# Display.net
KiCad netlist of a schematic drawn in Altium Designer
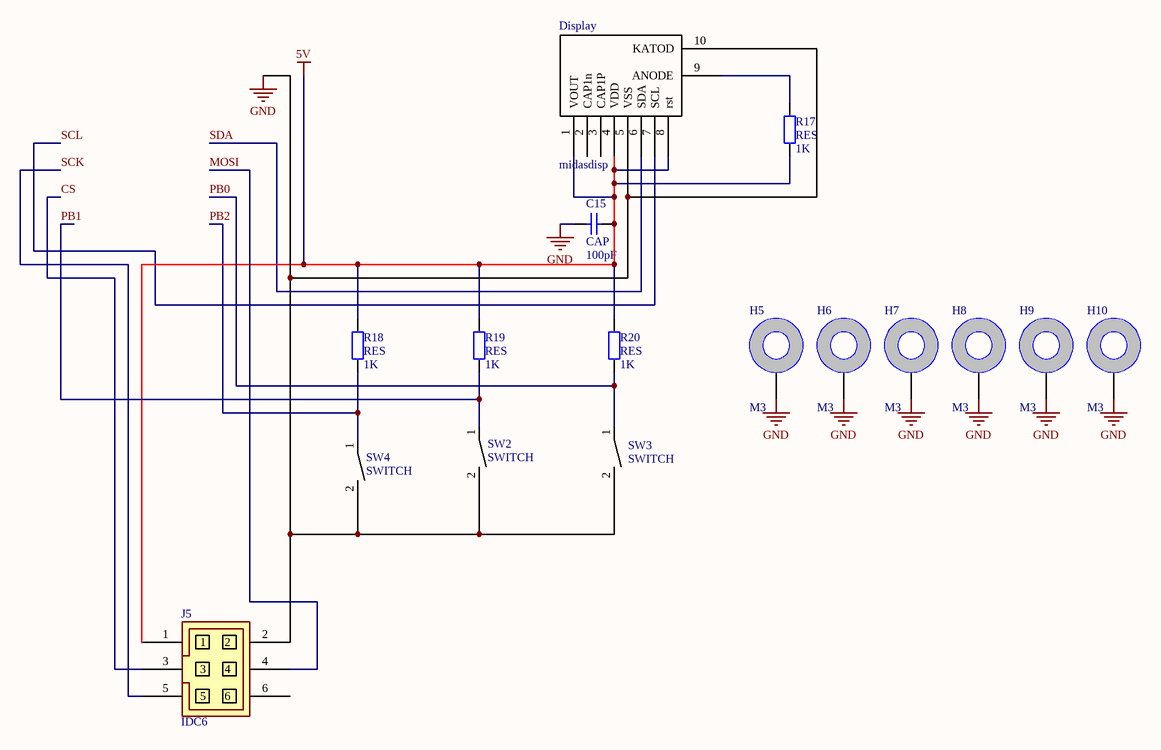
[diagram p0: Display.SchDoc]

(export (version "E")
  (design (tool "Eeschema 10.0.6"))
  (components
    (comp (ref "C15")
      (value "CAP")
      (footprint "CAPC1608X08M")
      (description "Capacitor")
      (fields (field (name "ALTIUM_VALUE") "100pF") (field (name "PUBLISHER") "Altium Limited"))
      (libsource (lib "std") (part "CAP"))
    )
    (comp (ref "Display")
      (value "midasdisp")
      (footprint "Display")
      (libsource (lib "MIDOSDISP") (part "midasdisp"))
    )
    (comp (ref "H5") (value "M3") (footprint "MOUNT_M3") (libsource (lib "std") (part "MOUNT_M3")))
    (comp (ref "H6") (value "M3") (footprint "MOUNT_M3") (libsource (lib "std") (part "MOUNT_M3")))
    (comp (ref "H7") (value "M3") (footprint "MOUNT_M3") (libsource (lib "std") (part "MOUNT_M3")))
    (comp (ref "H8") (value "M3") (footprint "MOUNT_M3") (libsource (lib "std") (part "MOUNT_M3")))
    (comp (ref "H9") (value "M3") (footprint "MOUNT_M3") (libsource (lib "std") (part "MOUNT_M3")))
    (comp (ref "H10") (value "M3") (footprint "MOUNT_M3") (libsource (lib "std") (part "MOUNT_M3")))
    (comp (ref "J5")
      (value "IDC6")
      (footprint "IDC6")
      (description "6pin IDC connector")
      (libsource (lib "std") (part "IDC6"))
    )
    (comp (ref "R17")
      (value "RES")
      (footprint "RESC1608X06M")
      (description "Resistor")
      (fields (field (name "ALTIUM_VALUE") "1K") (field (name "PUBLISHER") "Altium Limited"))
      (libsource (lib "std") (part "RES"))
    )
    (comp (ref "R18")
      (value "RES")
      (footprint "RESC1608X06M")
      (description "Resistor")
      (fields (field (name "ALTIUM_VALUE") "1K") (field (name "PUBLISHER") "Altium Limited"))
      (libsource (lib "std") (part "RES"))
    )
    (comp (ref "R19")
      (value "RES")
      (footprint "RESC1608X06M")
      (description "Resistor")
      (fields (field (name "ALTIUM_VALUE") "1K") (field (name "PUBLISHER") "Altium Limited"))
      (libsource (lib "std") (part "RES"))
    )
    (comp (ref "R20")
      (value "RES")
      (footprint "RESC1608X06M")
      (description "Resistor")
      (fields (field (name "ALTIUM_VALUE") "1K") (field (name "PUBLISHER") "Altium Limited"))
      (libsource (lib "std") (part "RES"))
    )
    (comp (ref "SW2")
      (value "SWITCH")
      (footprint "Switch_pad")
      (description "Switch")
      (libsource (lib "std") (part "Switch"))
    )
    (comp (ref "SW3")
      (value "SWITCH")
      (footprint "Switch_pad")
      (description "Switch")
      (libsource (lib "std") (part "Switch"))
    )
    (comp (ref "SW4")
      (value "SWITCH")
      (footprint "Switch_pad")
      (description "Switch")
      (libsource (lib "std") (part "Switch"))
    )
  )
  (nets
    (net (code "1") (name "/CS") (class "Default")
      (node (ref "J5") (pin "3") (pinfunction "3_3") (pintype "passive"))
    )
    (net (code "2") (name "/MOSI") (class "Default")
      (node (ref "J5") (pin "4") (pinfunction "4_4") (pintype "passive"))
    )
    (net (code "3") (name "/PB0") (class "Default")
      (node (ref "R20") (pin "1") (pinfunction "1_1") (pintype "passive"))
      (node (ref "SW3") (pin "1") (pinfunction "1_1") (pintype "passive"))
    )
    (net (code "4") (name "/PB1") (class "Default")
      (node (ref "R19") (pin "1") (pinfunction "1_1") (pintype "passive"))
      (node (ref "SW2") (pin "1") (pinfunction "1_1") (pintype "passive"))
    )
    (net (code "5") (name "/PB2") (class "Default")
      (node (ref "R18") (pin "1") (pinfunction "1_1") (pintype "passive"))
      (node (ref "SW4") (pin "1") (pinfunction "1_1") (pintype "passive"))
    )
    (net (code "6") (name "/SCK") (class "Default")
      (node (ref "J5") (pin "5") (pinfunction "5_5") (pintype "passive"))
    )
    (net (code "7") (name "/SCL") (class "Default")
      (node (ref "Display") (pin "7") (pinfunction "SCL_7") (pintype "passive"))
    )
    (net (code "8") (name "/SDA") (class "Default")
      (node (ref "Display") (pin "6") (pinfunction "SDA_6") (pintype "passive"))
    )
    (net (code "9") (name "5V") (class "Default")
      (node (ref "C15") (pin "2") (pinfunction "2_2") (pintype "passive"))
      (node (ref "Display") (pin "1") (pinfunction "VOUT_1") (pintype "passive"))
      (node (ref "Display") (pin "4") (pinfunction "VDD_4") (pintype "passive"))
      (node (ref "Display") (pin "8") (pinfunction "rst_8") (pintype "passive"))
      (node (ref "J5") (pin "1") (pinfunction "1_1") (pintype "passive"))
      (node (ref "R17") (pin "1") (pinfunction "1_1") (pintype "passive"))
      (node (ref "R18") (pin "2") (pinfunction "2_2") (pintype "passive"))
      (node (ref "R19") (pin "2") (pinfunction "2_2") (pintype "passive"))
      (node (ref "R20") (pin "2") (pinfunction "2_2") (pintype "passive"))
    )
    (net (code "10") (name "GND") (class "Default")
      (node (ref "C15") (pin "1") (pinfunction "1_1") (pintype "passive"))
      (node (ref "Display") (pin "10") (pinfunction "KATOD_10") (pintype "passive"))
      (node (ref "Display") (pin "5") (pinfunction "VSS_5") (pintype "passive"))
      (node (ref "H10") (pin "1") (pinfunction "1_1") (pintype "passive"))
      (node (ref "H5") (pin "1") (pinfunction "1_1") (pintype "passive"))
      (node (ref "H6") (pin "1") (pinfunction "1_1") (pintype "passive"))
      (node (ref "H7") (pin "1") (pinfunction "1_1") (pintype "passive"))
      (node (ref "H8") (pin "1") (pinfunction "1_1") (pintype "passive"))
      (node (ref "H9") (pin "1") (pinfunction "1_1") (pintype "passive"))
      (node (ref "J5") (pin "2") (pinfunction "2_2") (pintype "passive"))
      (node (ref "SW2") (pin "2") (pinfunction "2_2") (pintype "passive"))
      (node (ref "SW3") (pin "2") (pinfunction "2_2") (pintype "passive"))
      (node (ref "SW4") (pin "2") (pinfunction "2_2") (pintype "passive"))
    )
    (net (code "11") (name "Net-(Display-ANODE)") (class "Default")
      (node (ref "Display") (pin "9") (pinfunction "ANODE_9") (pintype "passive"))
      (node (ref "R17") (pin "2") (pinfunction "2_2") (pintype "passive"))
    )
    (net (code "12") (name "unconnected-(Display-CAP1P-Pad3)") (class "Default")
      (node (ref "Display") (pin "3") (pinfunction "CAP1P_3") (pintype "passive"))
    )
    (net (code "13") (name "unconnected-(Display-CAP1n-Pad2)") (class "Default")
      (node (ref "Display") (pin "2") (pinfunction "CAP1n_2") (pintype "passive"))
    )
    (net (code "14") (name "unconnected-(J5-Pad6)") (class "Default")
      (node (ref "J5") (pin "6") (pinfunction "6_6") (pintype "passive"))
    )
  )
)
